# brd-gates-low.net
KiCad netlist of a schematic drawn in EAGLE
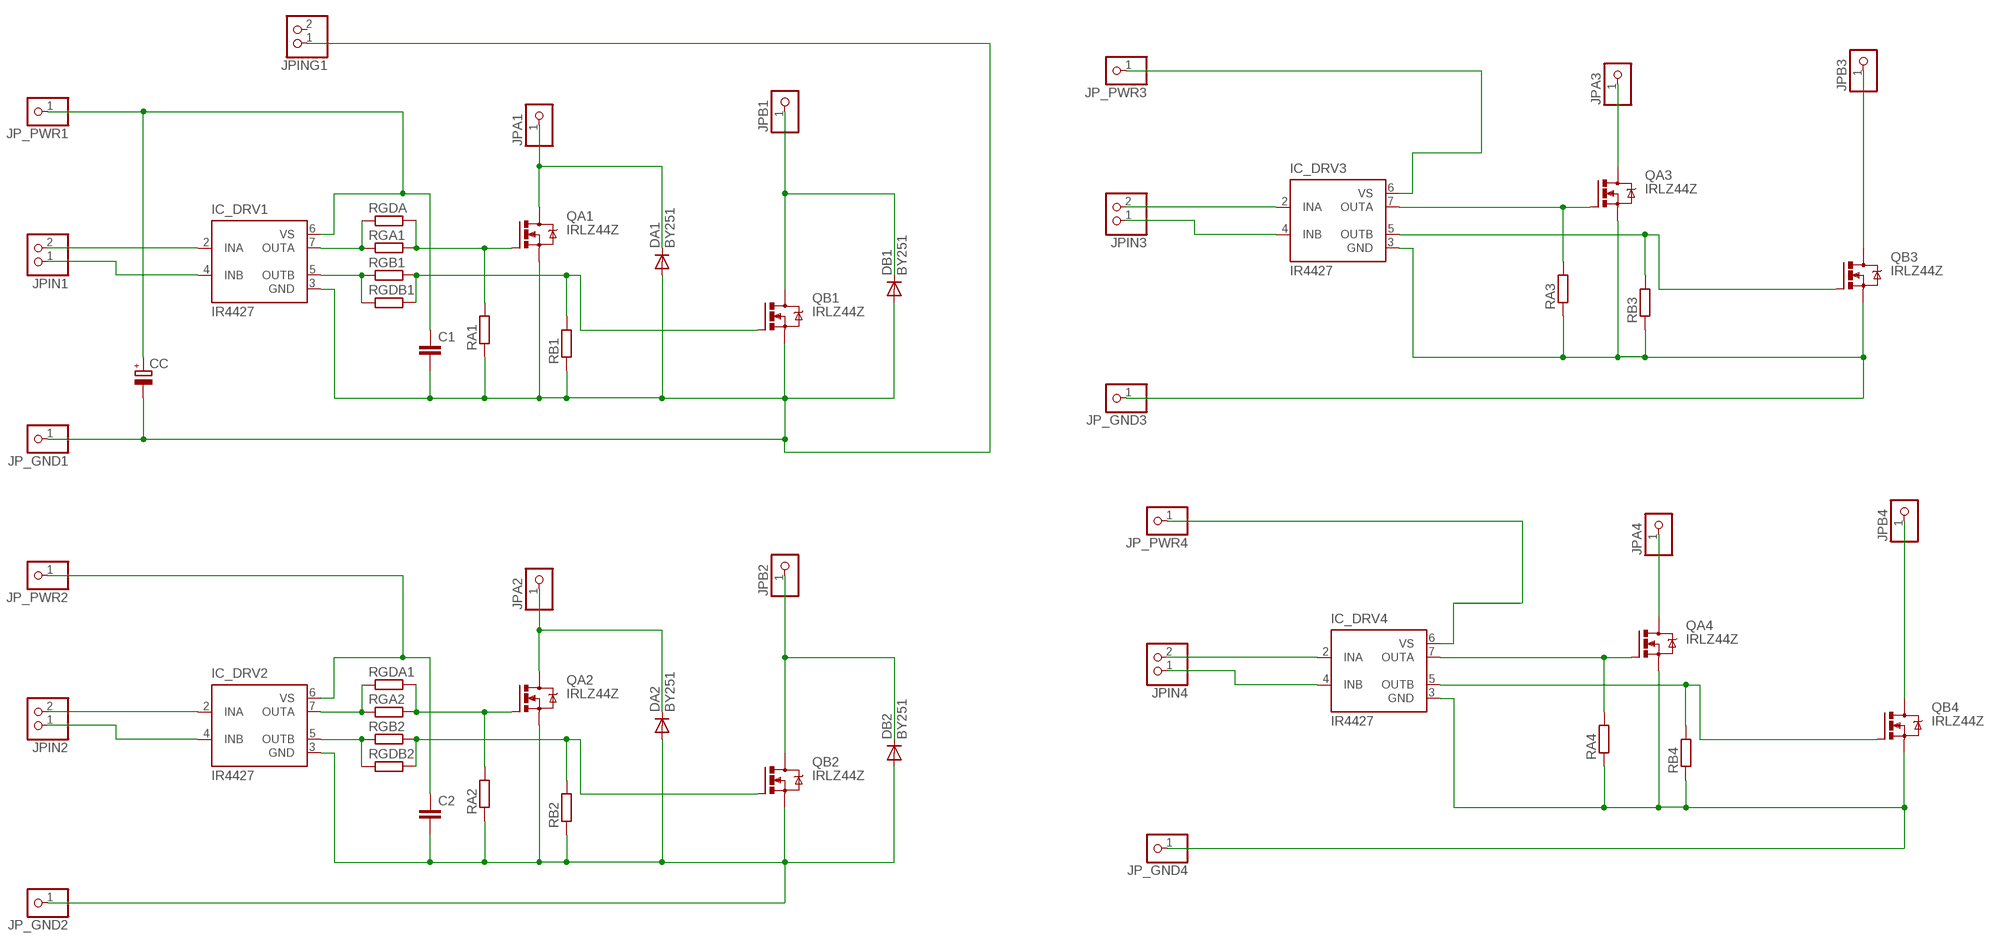
[diagram p0: schematic, sheet 1]

(export (version "E")
  (design (tool "Eeschema 10.0.6"))
  (components
    (comp (ref "C1")
      (value "C-EU050-055X075")
      (footprint "eagle-import:C050-055X075")
      (libsource (lib "eagle-import") (part "C-EU050-055X075"))
    )
    (comp (ref "C2")
      (value "C-EU050-055X075")
      (footprint "eagle-import:C050-055X075")
      (libsource (lib "eagle-import") (part "C-EU050-055X075"))
    )
    (comp (ref "CC")
      (value "CPOL-EUE5-13")
      (footprint "eagle-import:E5-13")
      (libsource (lib "eagle-import") (part "CPOL-EUE5-13"))
    )
    (comp (ref "DA1")
      (value "BY251")
      (footprint "eagle-import:DO201-15")
      (libsource (lib "eagle-import") (part "BY251"))
    )
    (comp (ref "DA2")
      (value "BY251")
      (footprint "eagle-import:DO201-15")
      (libsource (lib "eagle-import") (part "BY251"))
    )
    (comp (ref "DB1")
      (value "BY251")
      (footprint "eagle-import:DO201-15")
      (libsource (lib "eagle-import") (part "BY251"))
    )
    (comp (ref "DB2")
      (value "BY251")
      (footprint "eagle-import:DO201-15")
      (libsource (lib "eagle-import") (part "BY251"))
    )
    (comp (ref "IC_DRV1")
      (value "IR4427")
      (footprint "eagle-import:DIL08")
      (fields (field (name "MF") "INTERNATIONAL RECTIFIER(IR)"))
      (libsource (lib "eagle-import") (part "IR4427"))
    )
    (comp (ref "IC_DRV2")
      (value "IR4427")
      (footprint "eagle-import:DIL08")
      (fields (field (name "MF") "INTERNATIONAL RECTIFIER(IR)"))
      (libsource (lib "eagle-import") (part "IR4427"))
    )
    (comp (ref "IC_DRV3")
      (value "IR4427")
      (footprint "eagle-import:DIL08")
      (fields (field (name "MF") "INTERNATIONAL RECTIFIER(IR)"))
      (libsource (lib "eagle-import") (part "IR4427"))
    )
    (comp (ref "IC_DRV4")
      (value "IR4427")
      (footprint "eagle-import:DIL08")
      (fields (field (name "MF") "INTERNATIONAL RECTIFIER(IR)"))
      (libsource (lib "eagle-import") (part "IR4427"))
    )
    (comp (ref "JPA1")
      (value "PINHD-1X1")
      (footprint "eagle-import:1X01")
      (libsource (lib "eagle-import") (part "PINHD-1X1"))
    )
    (comp (ref "JPA2")
      (value "PINHD-1X1")
      (footprint "eagle-import:1X01")
      (libsource (lib "eagle-import") (part "PINHD-1X1"))
    )
    (comp (ref "JPA3")
      (value "PINHD-1X1")
      (footprint "eagle-import:1X01")
      (libsource (lib "eagle-import") (part "PINHD-1X1"))
    )
    (comp (ref "JPA4")
      (value "PINHD-1X1")
      (footprint "eagle-import:1X01")
      (libsource (lib "eagle-import") (part "PINHD-1X1"))
    )
    (comp (ref "JPB1")
      (value "PINHD-1X1")
      (footprint "eagle-import:1X01")
      (libsource (lib "eagle-import") (part "PINHD-1X1"))
    )
    (comp (ref "JPB2")
      (value "PINHD-1X1")
      (footprint "eagle-import:1X01")
      (libsource (lib "eagle-import") (part "PINHD-1X1"))
    )
    (comp (ref "JPB3")
      (value "PINHD-1X1")
      (footprint "eagle-import:1X01")
      (libsource (lib "eagle-import") (part "PINHD-1X1"))
    )
    (comp (ref "JPB4")
      (value "PINHD-1X1")
      (footprint "eagle-import:1X01")
      (libsource (lib "eagle-import") (part "PINHD-1X1"))
    )
    (comp (ref "JPIN1")
      (value "PINHD-1X2")
      (footprint "eagle-import:1X02")
      (libsource (lib "eagle-import") (part "PINHD-1X2"))
    )
    (comp (ref "JPIN2")
      (value "PINHD-1X2")
      (footprint "eagle-import:1X02")
      (libsource (lib "eagle-import") (part "PINHD-1X2"))
    )
    (comp (ref "JPIN3")
      (value "PINHD-1X2")
      (footprint "eagle-import:1X02")
      (libsource (lib "eagle-import") (part "PINHD-1X2"))
    )
    (comp (ref "JPIN4")
      (value "PINHD-1X2")
      (footprint "eagle-import:1X02")
      (libsource (lib "eagle-import") (part "PINHD-1X2"))
    )
    (comp (ref "JPING1")
      (value "PINHD-1X2")
      (footprint "eagle-import:1X02")
      (libsource (lib "eagle-import") (part "PINHD-1X2"))
    )
    (comp (ref "JP_GND1")
      (value "PINHD-1X1")
      (footprint "eagle-import:1X01")
      (libsource (lib "eagle-import") (part "PINHD-1X1"))
    )
    (comp (ref "JP_GND2")
      (value "PINHD-1X1")
      (footprint "eagle-import:1X01")
      (libsource (lib "eagle-import") (part "PINHD-1X1"))
    )
    (comp (ref "JP_GND3")
      (value "PINHD-1X1")
      (footprint "eagle-import:1X01")
      (libsource (lib "eagle-import") (part "PINHD-1X1"))
    )
    (comp (ref "JP_GND4")
      (value "PINHD-1X1")
      (footprint "eagle-import:1X01")
      (libsource (lib "eagle-import") (part "PINHD-1X1"))
    )
    (comp (ref "JP_PWR1")
      (value "PINHD-1X1")
      (footprint "eagle-import:1X01")
      (libsource (lib "eagle-import") (part "PINHD-1X1"))
    )
    (comp (ref "JP_PWR2")
      (value "PINHD-1X1")
      (footprint "eagle-import:1X01")
      (libsource (lib "eagle-import") (part "PINHD-1X1"))
    )
    (comp (ref "JP_PWR3")
      (value "PINHD-1X1")
      (footprint "eagle-import:1X01")
      (libsource (lib "eagle-import") (part "PINHD-1X1"))
    )
    (comp (ref "JP_PWR4")
      (value "PINHD-1X1")
      (footprint "eagle-import:1X01")
      (libsource (lib "eagle-import") (part "PINHD-1X1"))
    )
    (comp (ref "QA1")
      (value "IRLZ44Z")
      (footprint "eagle-import:TO220BH")
      (libsource (lib "eagle-import") (part "IRLZ44Z"))
    )
    (comp (ref "QA2")
      (value "IRLZ44Z")
      (footprint "eagle-import:TO220BH")
      (libsource (lib "eagle-import") (part "IRLZ44Z"))
    )
    (comp (ref "QA3")
      (value "IRLZ44Z")
      (footprint "eagle-import:TO220BH")
      (libsource (lib "eagle-import") (part "IRLZ44Z"))
    )
    (comp (ref "QA4")
      (value "IRLZ44Z")
      (footprint "eagle-import:TO220BH")
      (libsource (lib "eagle-import") (part "IRLZ44Z"))
    )
    (comp (ref "QB1")
      (value "IRLZ44Z")
      (footprint "eagle-import:TO220BH")
      (libsource (lib "eagle-import") (part "IRLZ44Z"))
    )
    (comp (ref "QB2")
      (value "IRLZ44Z")
      (footprint "eagle-import:TO220BH")
      (libsource (lib "eagle-import") (part "IRLZ44Z"))
    )
    (comp (ref "QB3")
      (value "IRLZ44Z")
      (footprint "eagle-import:TO220BH")
      (libsource (lib "eagle-import") (part "IRLZ44Z"))
    )
    (comp (ref "QB4")
      (value "IRLZ44Z")
      (footprint "eagle-import:TO220BH")
      (libsource (lib "eagle-import") (part "IRLZ44Z"))
    )
    (comp (ref "RA1")
      (value "R-EU_0207/10")
      (footprint "eagle-import:0207_10")
      (libsource (lib "eagle-import") (part "R-EU_0207/10"))
    )
    (comp (ref "RA2")
      (value "R-EU_0207/10")
      (footprint "eagle-import:0207_10")
      (libsource (lib "eagle-import") (part "R-EU_0207/10"))
    )
    (comp (ref "RA3")
      (value "R-EU_0207/10")
      (footprint "eagle-import:0207_10")
      (libsource (lib "eagle-import") (part "R-EU_0207/10"))
    )
    (comp (ref "RA4")
      (value "R-EU_0207/10")
      (footprint "eagle-import:0207_10")
      (libsource (lib "eagle-import") (part "R-EU_0207/10"))
    )
    (comp (ref "RB1")
      (value "R-EU_0207/10")
      (footprint "eagle-import:0207_10")
      (libsource (lib "eagle-import") (part "R-EU_0207/10"))
    )
    (comp (ref "RB2")
      (value "R-EU_0207/10")
      (footprint "eagle-import:0207_10")
      (libsource (lib "eagle-import") (part "R-EU_0207/10"))
    )
    (comp (ref "RB3")
      (value "R-EU_0207/10")
      (footprint "eagle-import:0207_10")
      (libsource (lib "eagle-import") (part "R-EU_0207/10"))
    )
    (comp (ref "RB4")
      (value "R-EU_0207/10")
      (footprint "eagle-import:0207_10")
      (libsource (lib "eagle-import") (part "R-EU_0207/10"))
    )
    (comp (ref "RGA1")
      (value "R-EU_0207/10")
      (footprint "eagle-import:0207_10")
      (libsource (lib "eagle-import") (part "R-EU_0207/10"))
    )
    (comp (ref "RGA2")
      (value "R-EU_0207/10")
      (footprint "eagle-import:0207_10")
      (libsource (lib "eagle-import") (part "R-EU_0207/10"))
    )
    (comp (ref "RGB1")
      (value "R-EU_0207/10")
      (footprint "eagle-import:0207_10")
      (libsource (lib "eagle-import") (part "R-EU_0207/10"))
    )
    (comp (ref "RGB2")
      (value "R-EU_0207/10")
      (footprint "eagle-import:0207_10")
      (libsource (lib "eagle-import") (part "R-EU_0207/10"))
    )
    (comp (ref "RGDA")
      (value "R-EU_0207/10")
      (footprint "eagle-import:0207_10")
      (libsource (lib "eagle-import") (part "R-EU_0207/10"))
    )
    (comp (ref "RGDA1")
      (value "R-EU_0207/10")
      (footprint "eagle-import:0207_10")
      (libsource (lib "eagle-import") (part "R-EU_0207/10"))
    )
    (comp (ref "RGDB1")
      (value "R-EU_0207/10")
      (footprint "eagle-import:0207_10")
      (libsource (lib "eagle-import") (part "R-EU_0207/10"))
    )
    (comp (ref "RGDB2")
      (value "R-EU_0207/10")
      (footprint "eagle-import:0207_10")
      (libsource (lib "eagle-import") (part "R-EU_0207/10"))
    )
  )
  (nets
    (net (code "1") (name "Net-(DA1-PadC)") (class "Default")
      (node (ref "DA1") (pin "C") (pinfunction "C_C") (pintype "passive"))
      (node (ref "JPA1") (pin "1") (pinfunction "1_1") (pintype "passive"))
      (node (ref "QA1") (pin "D") (pinfunction "D_D") (pintype "passive"))
    )
    (net (code "2") (name "Net-(DA2-PadC)") (class "Default")
      (node (ref "DA2") (pin "C") (pinfunction "C_C") (pintype "passive"))
      (node (ref "JPA2") (pin "1") (pinfunction "1_1") (pintype "passive"))
      (node (ref "QA2") (pin "D") (pinfunction "D_D") (pintype "passive"))
    )
    (net (code "3") (name "Net-(DB1-PadC)") (class "Default")
      (node (ref "DB1") (pin "C") (pinfunction "C_C") (pintype "passive"))
      (node (ref "JPB1") (pin "1") (pinfunction "1_1") (pintype "passive"))
      (node (ref "QB1") (pin "D") (pinfunction "D_D") (pintype "passive"))
    )
    (net (code "4") (name "Net-(DB2-PadC)") (class "Default")
      (node (ref "DB2") (pin "C") (pinfunction "C_C") (pintype "passive"))
      (node (ref "JPB2") (pin "1") (pinfunction "1_1") (pintype "passive"))
      (node (ref "QB2") (pin "D") (pinfunction "D_D") (pintype "passive"))
    )
    (net (code "5") (name "Net-(IC_DRV1-GND)") (class "Default")
      (node (ref "C1") (pin "2") (pinfunction "2_2") (pintype "passive"))
      (node (ref "CC") (pin "-") (pinfunction "-_-") (pintype "passive"))
      (node (ref "DA1") (pin "A") (pinfunction "A_A") (pintype "passive"))
      (node (ref "DB1") (pin "A") (pinfunction "A_A") (pintype "passive"))
      (node (ref "IC_DRV1") (pin "3") (pinfunction "GND_3") (pintype "power_in"))
      (node (ref "JPING1") (pin "1") (pinfunction "1_1") (pintype "passive"))
      (node (ref "JP_GND1") (pin "1") (pinfunction "1_1") (pintype "passive"))
      (node (ref "QA1") (pin "S") (pinfunction "S_S") (pintype "passive"))
      (node (ref "QB1") (pin "S") (pinfunction "S_S") (pintype "passive"))
      (node (ref "RA1") (pin "1") (pinfunction "1_1") (pintype "passive"))
      (node (ref "RB1") (pin "1") (pinfunction "1_1") (pintype "passive"))
    )
    (net (code "6") (name "Net-(IC_DRV1-INA)") (class "Default")
      (node (ref "IC_DRV1") (pin "2") (pinfunction "INA_2") (pintype "input"))
      (node (ref "JPIN1") (pin "2") (pinfunction "2_2") (pintype "passive"))
    )
    (net (code "7") (name "Net-(IC_DRV1-INB)") (class "Default")
      (node (ref "IC_DRV1") (pin "4") (pinfunction "INB_4") (pintype "input"))
      (node (ref "JPIN1") (pin "1") (pinfunction "1_1") (pintype "passive"))
    )
    (net (code "8") (name "Net-(IC_DRV1-OUTA)") (class "Default")
      (node (ref "IC_DRV1") (pin "7") (pinfunction "OUTA_7") (pintype "output"))
      (node (ref "RGA1") (pin "1") (pinfunction "1_1") (pintype "passive"))
      (node (ref "RGDA") (pin "1") (pinfunction "1_1") (pintype "passive"))
    )
    (net (code "9") (name "Net-(IC_DRV1-OUTB)") (class "Default")
      (node (ref "IC_DRV1") (pin "5") (pinfunction "OUTB_5") (pintype "output"))
      (node (ref "RGB1") (pin "1") (pinfunction "1_1") (pintype "passive"))
      (node (ref "RGDB1") (pin "1") (pinfunction "1_1") (pintype "passive"))
    )
    (net (code "10") (name "Net-(IC_DRV1-VS)") (class "Default")
      (node (ref "C1") (pin "1") (pinfunction "1_1") (pintype "passive"))
      (node (ref "CC") (pin "+") (pinfunction "+_+") (pintype "passive"))
      (node (ref "IC_DRV1") (pin "6") (pinfunction "VS_6") (pintype "power_in"))
      (node (ref "JP_PWR1") (pin "1") (pinfunction "1_1") (pintype "passive"))
    )
    (net (code "11") (name "Net-(IC_DRV2-GND)") (class "Default")
      (node (ref "C2") (pin "2") (pinfunction "2_2") (pintype "passive"))
      (node (ref "DA2") (pin "A") (pinfunction "A_A") (pintype "passive"))
      (node (ref "DB2") (pin "A") (pinfunction "A_A") (pintype "passive"))
      (node (ref "IC_DRV2") (pin "3") (pinfunction "GND_3") (pintype "power_in"))
      (node (ref "JP_GND2") (pin "1") (pinfunction "1_1") (pintype "passive"))
      (node (ref "QA2") (pin "S") (pinfunction "S_S") (pintype "passive"))
      (node (ref "QB2") (pin "S") (pinfunction "S_S") (pintype "passive"))
      (node (ref "RA2") (pin "1") (pinfunction "1_1") (pintype "passive"))
      (node (ref "RB2") (pin "1") (pinfunction "1_1") (pintype "passive"))
    )
    (net (code "12") (name "Net-(IC_DRV2-INA)") (class "Default")
      (node (ref "IC_DRV2") (pin "2") (pinfunction "INA_2") (pintype "input"))
      (node (ref "JPIN2") (pin "2") (pinfunction "2_2") (pintype "passive"))
    )
    (net (code "13") (name "Net-(IC_DRV2-INB)") (class "Default")
      (node (ref "IC_DRV2") (pin "4") (pinfunction "INB_4") (pintype "input"))
      (node (ref "JPIN2") (pin "1") (pinfunction "1_1") (pintype "passive"))
    )
    (net (code "14") (name "Net-(IC_DRV2-OUTA)") (class "Default")
      (node (ref "IC_DRV2") (pin "7") (pinfunction "OUTA_7") (pintype "output"))
      (node (ref "RGA2") (pin "1") (pinfunction "1_1") (pintype "passive"))
      (node (ref "RGDA1") (pin "1") (pinfunction "1_1") (pintype "passive"))
    )
    (net (code "15") (name "Net-(IC_DRV2-OUTB)") (class "Default")
      (node (ref "IC_DRV2") (pin "5") (pinfunction "OUTB_5") (pintype "output"))
      (node (ref "RGB2") (pin "1") (pinfunction "1_1") (pintype "passive"))
      (node (ref "RGDB2") (pin "1") (pinfunction "1_1") (pintype "passive"))
    )
    (net (code "16") (name "Net-(IC_DRV2-VS)") (class "Default")
      (node (ref "C2") (pin "1") (pinfunction "1_1") (pintype "passive"))
      (node (ref "IC_DRV2") (pin "6") (pinfunction "VS_6") (pintype "power_in"))
      (node (ref "JP_PWR2") (pin "1") (pinfunction "1_1") (pintype "passive"))
    )
    (net (code "17") (name "Net-(IC_DRV3-GND)") (class "Default")
      (node (ref "IC_DRV3") (pin "3") (pinfunction "GND_3") (pintype "power_in"))
      (node (ref "JP_GND3") (pin "1") (pinfunction "1_1") (pintype "passive"))
      (node (ref "QA3") (pin "S") (pinfunction "S_S") (pintype "passive"))
      (node (ref "QB3") (pin "S") (pinfunction "S_S") (pintype "passive"))
      (node (ref "RA3") (pin "1") (pinfunction "1_1") (pintype "passive"))
      (node (ref "RB3") (pin "1") (pinfunction "1_1") (pintype "passive"))
    )
    (net (code "18") (name "Net-(IC_DRV3-INA)") (class "Default")
      (node (ref "IC_DRV3") (pin "2") (pinfunction "INA_2") (pintype "input"))
      (node (ref "JPIN3") (pin "2") (pinfunction "2_2") (pintype "passive"))
    )
    (net (code "19") (name "Net-(IC_DRV3-INB)") (class "Default")
      (node (ref "IC_DRV3") (pin "4") (pinfunction "INB_4") (pintype "input"))
      (node (ref "JPIN3") (pin "1") (pinfunction "1_1") (pintype "passive"))
    )
    (net (code "20") (name "Net-(IC_DRV3-OUTA)") (class "Default")
      (node (ref "IC_DRV3") (pin "7") (pinfunction "OUTA_7") (pintype "output"))
      (node (ref "QA3") (pin "G") (pinfunction "G_G") (pintype "passive"))
      (node (ref "RA3") (pin "2") (pinfunction "2_2") (pintype "passive"))
    )
    (net (code "21") (name "Net-(IC_DRV3-OUTB)") (class "Default")
      (node (ref "IC_DRV3") (pin "5") (pinfunction "OUTB_5") (pintype "output"))
      (node (ref "QB3") (pin "G") (pinfunction "G_G") (pintype "passive"))
      (node (ref "RB3") (pin "2") (pinfunction "2_2") (pintype "passive"))
    )
    (net (code "22") (name "Net-(IC_DRV3-VS)") (class "Default")
      (node (ref "IC_DRV3") (pin "6") (pinfunction "VS_6") (pintype "power_in"))
      (node (ref "JP_PWR3") (pin "1") (pinfunction "1_1") (pintype "passive"))
    )
    (net (code "23") (name "Net-(IC_DRV4-GND)") (class "Default")
      (node (ref "IC_DRV4") (pin "3") (pinfunction "GND_3") (pintype "power_in"))
      (node (ref "JP_GND4") (pin "1") (pinfunction "1_1") (pintype "passive"))
      (node (ref "QA4") (pin "S") (pinfunction "S_S") (pintype "passive"))
      (node (ref "QB4") (pin "S") (pinfunction "S_S") (pintype "passive"))
      (node (ref "RA4") (pin "1") (pinfunction "1_1") (pintype "passive"))
      (node (ref "RB4") (pin "1") (pinfunction "1_1") (pintype "passive"))
    )
    (net (code "24") (name "Net-(IC_DRV4-INA)") (class "Default")
      (node (ref "IC_DRV4") (pin "2") (pinfunction "INA_2") (pintype "input"))
      (node (ref "JPIN4") (pin "2") (pinfunction "2_2") (pintype "passive"))
    )
    (net (code "25") (name "Net-(IC_DRV4-INB)") (class "Default")
      (node (ref "IC_DRV4") (pin "4") (pinfunction "INB_4") (pintype "input"))
      (node (ref "JPIN4") (pin "1") (pinfunction "1_1") (pintype "passive"))
    )
    (net (code "26") (name "Net-(IC_DRV4-OUTA)") (class "Default")
      (node (ref "IC_DRV4") (pin "7") (pinfunction "OUTA_7") (pintype "output"))
      (node (ref "QA4") (pin "G") (pinfunction "G_G") (pintype "passive"))
      (node (ref "RA4") (pin "2") (pinfunction "2_2") (pintype "passive"))
    )
    (net (code "27") (name "Net-(IC_DRV4-OUTB)") (class "Default")
      (node (ref "IC_DRV4") (pin "5") (pinfunction "OUTB_5") (pintype "output"))
      (node (ref "QB4") (pin "G") (pinfunction "G_G") (pintype "passive"))
      (node (ref "RB4") (pin "2") (pinfunction "2_2") (pintype "passive"))
    )
    (net (code "28") (name "Net-(IC_DRV4-VS)") (class "Default")
      (node (ref "IC_DRV4") (pin "6") (pinfunction "VS_6") (pintype "power_in"))
      (node (ref "JP_PWR4") (pin "1") (pinfunction "1_1") (pintype "passive"))
    )
    (net (code "29") (name "Net-(JPA3-Pad1)") (class "Default")
      (node (ref "JPA3") (pin "1") (pinfunction "1_1") (pintype "passive"))
      (node (ref "QA3") (pin "D") (pinfunction "D_D") (pintype "passive"))
    )
    (net (code "30") (name "Net-(JPA4-Pad1)") (class "Default")
      (node (ref "JPA4") (pin "1") (pinfunction "1_1") (pintype "passive"))
      (node (ref "QA4") (pin "D") (pinfunction "D_D") (pintype "passive"))
    )
    (net (code "31") (name "Net-(JPB3-Pad1)") (class "Default")
      (node (ref "JPB3") (pin "1") (pinfunction "1_1") (pintype "passive"))
      (node (ref "QB3") (pin "D") (pinfunction "D_D") (pintype "passive"))
    )
    (net (code "32") (name "Net-(JPB4-Pad1)") (class "Default")
      (node (ref "JPB4") (pin "1") (pinfunction "1_1") (pintype "passive"))
      (node (ref "QB4") (pin "D") (pinfunction "D_D") (pintype "passive"))
    )
    (net (code "33") (name "Net-(QA1-PadG)") (class "Default")
      (node (ref "QA1") (pin "G") (pinfunction "G_G") (pintype "passive"))
      (node (ref "RA1") (pin "2") (pinfunction "2_2") (pintype "passive"))
      (node (ref "RGA1") (pin "2") (pinfunction "2_2") (pintype "passive"))
      (node (ref "RGDA") (pin "2") (pinfunction "2_2") (pintype "passive"))
    )
    (net (code "34") (name "Net-(QA2-PadG)") (class "Default")
      (node (ref "QA2") (pin "G") (pinfunction "G_G") (pintype "passive"))
      (node (ref "RA2") (pin "2") (pinfunction "2_2") (pintype "passive"))
      (node (ref "RGA2") (pin "2") (pinfunction "2_2") (pintype "passive"))
      (node (ref "RGDA1") (pin "2") (pinfunction "2_2") (pintype "passive"))
    )
    (net (code "35") (name "Net-(QB1-PadG)") (class "Default")
      (node (ref "QB1") (pin "G") (pinfunction "G_G") (pintype "passive"))
      (node (ref "RB1") (pin "2") (pinfunction "2_2") (pintype "passive"))
      (node (ref "RGB1") (pin "2") (pinfunction "2_2") (pintype "passive"))
      (node (ref "RGDB1") (pin "2") (pinfunction "2_2") (pintype "passive"))
    )
    (net (code "36") (name "Net-(QB2-PadG)") (class "Default")
      (node (ref "QB2") (pin "G") (pinfunction "G_G") (pintype "passive"))
      (node (ref "RB2") (pin "2") (pinfunction "2_2") (pintype "passive"))
      (node (ref "RGB2") (pin "2") (pinfunction "2_2") (pintype "passive"))
      (node (ref "RGDB2") (pin "2") (pinfunction "2_2") (pintype "passive"))
    )
    (net (code "37") (name "unconnected-(JPING1-Pad2)") (class "Default")
      (node (ref "JPING1") (pin "2") (pinfunction "2_2") (pintype "passive"))
    )
  )
)
